# Main.net
KiCad netlist of a schematic drawn in Altium Designer
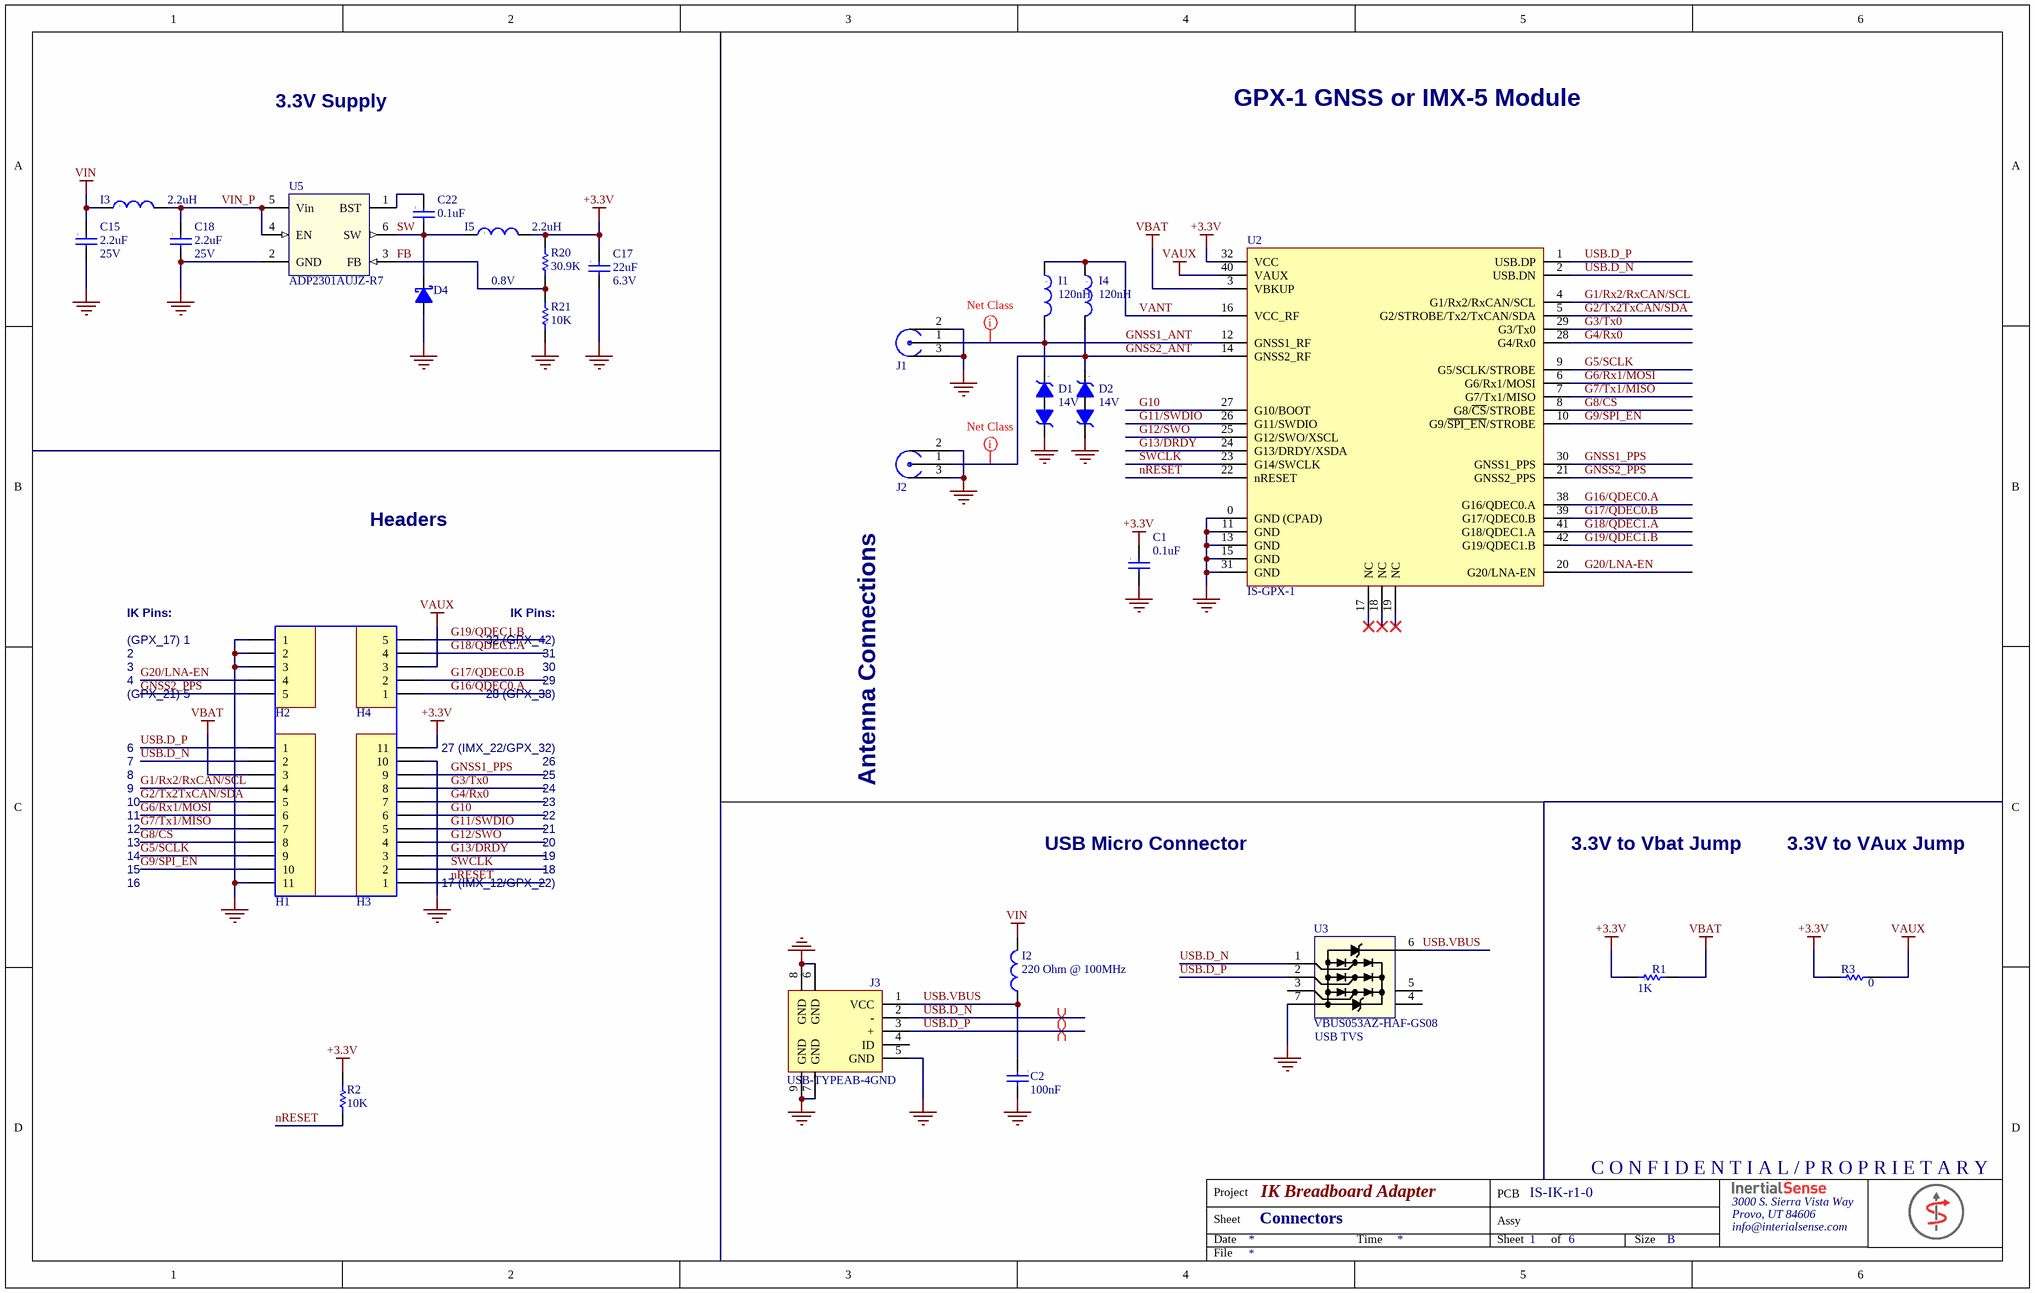
[diagram p0: Main.SchDoc]

(export (version "E")
  (design (tool "Eeschema 10.0.6"))
  (components
    (comp (ref "C1")
      (value "0.1uF")
      (footprint "0402")
      (description "CAP CER .10UF 50V X7R 10% 0402")
      (fields
        (field (name "MANUFACTURER") "TDK Corporation")
        (field (name "MANUFACTURER PART NUMBER") "C1005X7R1H104K")
        (field (name "PUBLISHER") "Altium Limited")
      )
      (libsource (lib "General") (part "Cap"))
    )
    (comp (ref "C2")
      (value "100nF")
      (footprint "0402")
      (description "CAP CER .10UF 50V X7R 10% 0402")
      (fields
        (field (name "MANUFACTURER") "TDK Corporation")
        (field (name "MANUFACTURER PART NUMBER") "C1005X7R1H104K")
        (field (name "PUBLISHER") "Altium Limited")
      )
      (libsource (lib "General") (part "Cap"))
    )
    (comp (ref "C15")
      (value "2.2uF")
      (footprint "0603")
      (description "CAP CER 2.2UF 25V X6S 0603")
      (fields
        (field (name "MANUFACTURER") "Murata")
        (field (name "MANUFACTURER PART NUMBER") "GRT188C81E225KE13D")
        (field (name "VOLTAGE RATING") "25V")
        (field (name "PUBLISHER") "Altium Limited")
      )
      (libsource (lib "General") (part "Cap"))
    )
    (comp (ref "C17")
      (value "22uF")
      (footprint "0603")
      (description "CAP CER 22UF 6.3V X6S 0603")
      (fields
        (field (name "MANUFACTURER") "Murata")
        (field (name "MANUFACTURER PART NUMBER") "GRM188C80J226ME15D")
        (field (name "VOLTAGE RATING") "6.3V")
        (field (name "PUBLISHER") "Altium Limited")
      )
      (libsource (lib "General") (part "Cap"))
    )
    (comp (ref "C18")
      (value "2.2uF")
      (footprint "0603")
      (description "CAP CER 2.2UF 25V X6S 0603")
      (fields
        (field (name "MANUFACTURER") "Murata")
        (field (name "MANUFACTURER PART NUMBER") "GRT188C81E225KE13D")
        (field (name "VOLTAGE RATING") "25V")
        (field (name "PUBLISHER") "Altium Limited")
      )
      (libsource (lib "General") (part "Cap"))
    )
    (comp (ref "C22")
      (value "0.1uF")
      (footprint "0402")
      (description "CAP CER 0.1UF 50V X7R 0402")
      (fields
        (field (name "MANUFACTURER") "TDK")
        (field (name "MANUFACTURER PART NUMBER") "CGA2B3X7R1H104K050BB")
        (field (name "PUBLISHER") "Altium Limited")
      )
      (libsource (lib "General") (part "Cap"))
    )
    (comp (ref "D1")
      (value "Diode - Bidirectional Zener")
      (footprint "R0402")
      (description "LITTELFUSE - PESD0402-140 - DIODE, ESD PROTECTION, 0402, FULL REEL")
      (fields
        (field (name "MANUFACTURER") "Littelfuse")
        (field (name "MANUFACTURER PART NUMBER") "PESD0402-140")
        (field (name "WORKING VOLTAGE") "14V")
      )
      (libsource (lib "General") (part "Diode - Bidirectional Zener"))
    )
    (comp (ref "D2")
      (value "Diode - Bidirectional Zener")
      (footprint "R0402")
      (description "LITTELFUSE - PESD0402-140 - DIODE, ESD PROTECTION, 0402, FULL REEL")
      (fields
        (field (name "MANUFACTURER") "Littelfuse")
        (field (name "MANUFACTURER PART NUMBER") "PESD0402-140")
        (field (name "WORKING VOLTAGE") "14V")
      )
      (libsource (lib "General") (part "Diode - Bidirectional Zener"))
    )
    (comp (ref "D4")
      (value "Diode - Schottky")
      (footprint "D0603B")
      (description "DIODE SCHOTTKY 30V 2A 0603")
      (fields
        (field (name "MANUFACTURER") "Vishay")
        (field (name "MANUFACTURER PART NUMBER") "VSKY20301608-G4-08")
      )
      (libsource (lib "General") (part "Diode - Schottky"))
    )
    (comp (ref "H1")
      (value "Hdr - 11pin")
      (footprint "Header-.1IN-1x11")
      (description "11 pin header")
      (libsource (lib "") (part "Hdr - 11pin_1"))
    )
    (comp (ref "H2")
      (value "Hdr - 5pin")
      (footprint "Header-.1IN-1x5")
      (description "5 pin header")
      (libsource (lib "") (part "Hdr - 5pin_1"))
    )
    (comp (ref "H3")
      (value "Hdr - 11pin")
      (footprint "Header-.1IN-1x11")
      (description "11 pin header")
      (libsource (lib "IS-IG-BB") (part "Hdr - 11pin"))
    )
    (comp (ref "H4")
      (value "Hdr - 5pin")
      (footprint "Header-.1IN-1x5")
      (description "5 pin header")
      (libsource (lib "IS-IG-BB") (part "Hdr - 5pin"))
    )
    (comp (ref "I1")
      (value "120nH")
      (footprint "0402")
      (description "Inductor RF Chip Wirewound 120nH 5% 100MHz 20Q-Factor 110mA 2.66Ohm DCR 0402 Paper T/R")
      (fields
        (field (name "MANUFACTURER") "Murata")
        (field (name "MANUFACTURER PART NUMBER") "LQW15ANR12J00D")
      )
      (libsource (lib "General") (part "Inductor"))
    )
    (comp (ref "I2")
      (value "220 Ohm @ 100MHz")
      (footprint "I0603")
      (description "FERRITE CHIP 220 OHM 2500MA 0603")
      (fields
        (field (name "MANUFACTURER") "Murata Electronics North America")
        (field (name "MANUFACTURER PART NUMBER") "BLM18SG221TN1D")
      )
      (libsource (lib "") (part "Inductor_1"))
    )
    (comp (ref "I3")
      (value "2.2uH")
      (footprint "0806")
      (description "FIXED IND 2.2UH 1.2A 110 MOHM")
      (fields
        (field (name "MANUFACTURER") "TDK")
        (field (name "MANUFACTURER PART NUMBER") "MLP2016H2R2MT0S1")
      )
      (libsource (lib "General") (part "Inductor"))
    )
    (comp (ref "I4")
      (value "120nH")
      (footprint "0402")
      (description "Inductor RF Chip Wirewound 120nH 5% 100MHz 20Q-Factor 110mA 2.66Ohm DCR 0402 Paper T/R")
      (fields
        (field (name "MANUFACTURER") "Murata")
        (field (name "MANUFACTURER PART NUMBER") "LQW15ANR12J00D")
      )
      (libsource (lib "General") (part "Inductor"))
    )
    (comp (ref "I5")
      (value "2.2uH")
      (footprint "0806")
      (description "FIXED IND 2.2UH 1.2A 110 MOHM")
      (fields
        (field (name "MANUFACTURER") "TDK")
        (field (name "MANUFACTURER PART NUMBER") "MLP2016H2R2MT0S1")
      )
      (libsource (lib "General") (part "Inductor"))
    )
    (comp (ref "J1")
      (value "RF - GND x 2")
      (footprint "RF UMC SMD")
      (description "CONN UMC RCPT STR 50 OHM SMD")
      (fields
        (field (name "MANUFACTURER") "Emerson Network Power Connectivity Johnson")
        (field (name "MANUFACTURER PART NUMBER") "128-0711-201")
      )
      (libsource (lib "Connectors") (part "RF - GND x 2"))
    )
    (comp (ref "J2")
      (value "RF - GND x 2")
      (footprint "RF UMC SMD")
      (description "CONN UMC RCPT STR 50 OHM SMD")
      (fields
        (field (name "MANUFACTURER") "Emerson Network Power Connectivity Johnson")
        (field (name "MANUFACTURER PART NUMBER") "128-0711-201")
      )
      (libsource (lib "Connectors") (part "RF - GND x 2"))
    )
    (comp (ref "J3")
      (value "USB-TYPEAB-4GND")
      (footprint "USB Micro AB R/A THR")
      (description "CONN USB AB 4POS")
      (fields
        (field (name "MANUFACTURER") "Amphenol FCI")
        (field (name "MANUFACTURER PART NUMBER") "10118194-0001LF")
      )
      (libsource (lib "Connectors") (part "USB-TYPEAB-4GND"))
    )
    (comp (ref "R1")
      (value "1K")
      (footprint "R0402")
      (description "1 kOhms ±1% 0.063W, 1/16W Chip Resistor 0402 (1005 Metric) Moisture Resistant Thick Film")
      (fields
        (field (name "MANUFACTURER") "Yageo")
        (field (name "MANUFACTURER PART NUMBER") "RC0402FR-071KL")
      )
      (libsource (lib "General") (part "Res"))
    )
    (comp (ref "R2")
      (value "10K")
      (footprint "R0402")
      (description "1 kOhms ±1% 0.063W, 1/16W Chip Resistor 0402 (1005 Metric) Moisture Resistant Thick Film")
      (fields
        (field (name "MANUFACTURER") "Stackpole Electronics")
        (field (name "MANUFACTURER PART NUMBER") "RMCF0402FT10K0")
      )
      (libsource (lib "General") (part "Res"))
    )
    (comp (ref "R3")
      (value "0")
      (footprint "R0402")
      (description "1 kOhms ±1% 0.063W, 1/16W Chip Resistor 0402 (1005 Metric) Moisture Resistant Thick Film")
      (fields
        (field (name "MANUFACTURER") "Yageo")
        (field (name "MANUFACTURER PART NUMBER") "RC0402FR-071KL")
      )
      (libsource (lib "General") (part "Res"))
    )
    (comp (ref "R20")
      (value "30.9K")
      (footprint "R0402")
      (description "RES TF 30.9K OHM 1% 1/16W 0402")
      (fields
        (field (name "MANUFACTURER") "Stackpole Electronics Inc")
        (field (name "MANUFACTURER PART NUMBER") "RMCF0402FT30K9")
      )
      (libsource (lib "General") (part "Res"))
    )
    (comp (ref "R21")
      (value "10K")
      (footprint "R0402")
      (description "RES 10.0K OHM 1/16W 1% 0402 SMD")
      (fields
        (field (name "MANUFACTURER") "Yageo")
        (field (name "MANUFACTURER PART NUMBER") "RC0402FR-0710KL")
      )
      (libsource (lib "General") (part "Res"))
    )
    (comp (ref "U2")
      (value "GPX")
      (footprint "IS-GPX-1.0")
      (description "Inertial Sense GPX")
      (fields
        (field (name "MANUFACTURER") "Inertial Sense")
        (field (name "MANUFACTURER PART NUMBER") "IS-GPX-1")
      )
      (libsource (lib "IS-GPX-1") (part "IS-GPX-1.0"))
    )
    (comp (ref "U3")
      (value "VBUS053")
      (footprint "QFN50P160X160X60-6N")
      (description "ESD SUPPRESS 5.5V 36W 3-Line USB")
      (fields
        (field (name "MANUFACTURER") "Vishay Semiconductors")
        (field (name "MANUFACTURER PART NUMBER") "VBUS053AZ-HAF-GS08")
      )
      (libsource (lib "ICs") (part "VBUS053"))
    )
    (comp (ref "U5")
      (value "ADP2301")
      (footprint "MO-178-AB")
      (description "IC BUCK ADJ 1.2A 6TSOT")
      (fields
        (field (name "MANUFACTURER") "Analog Devices Inc")
        (field (name "MANUFACTURER PART NUMBER") "ADP2301AUJZ-R7")
      )
      (libsource (lib "ICs") (part "ADP2301"))
    )
  )
  (nets
    (net (code "1") (name "+3.3V") (class "Default")
      (node (ref "C1") (pin "1") (pinfunction "1_1") (pintype "passive"))
      (node (ref "C17") (pin "1") (pinfunction "1_1") (pintype "passive"))
      (node (ref "H3") (pin "11") (pinfunction "11_11") (pintype "passive"))
      (node (ref "I5") (pin "2") (pinfunction "2_2") (pintype "passive"))
      (node (ref "R1") (pin "1") (pinfunction "1_1") (pintype "passive"))
      (node (ref "R2") (pin "1") (pinfunction "1_1") (pintype "passive"))
      (node (ref "R20") (pin "2") (pinfunction "2_2") (pintype "passive"))
      (node (ref "R3") (pin "1") (pinfunction "1_1") (pintype "passive"))
      (node (ref "U2") (pin "32") (pinfunction "VCC_32") (pintype "power_in"))
    )
    (net (code "2") (name "/FB") (class "Default")
      (node (ref "R20") (pin "1") (pinfunction "1_1") (pintype "passive"))
      (node (ref "R21") (pin "2") (pinfunction "2_2") (pintype "passive"))
      (node (ref "U5") (pin "3") (pinfunction "FB_3") (pintype "input"))
    )
    (net (code "3") (name "/G1{slash}Rx2{slash}RxCAN{slash}SCL") (class "Default")
      (node (ref "H1") (pin "4") (pinfunction "4_4") (pintype "passive"))
      (node (ref "U2") (pin "4") (pinfunction "G1/Rx2/RxCAN/SCL_4") (pintype "passive"))
    )
    (net (code "4") (name "/G2{slash}Tx2TxCAN{slash}SDA") (class "Default")
      (node (ref "H1") (pin "5") (pinfunction "5_5") (pintype "passive"))
      (node (ref "U2") (pin "5") (pinfunction "G2/STROBE/Tx2/TxCAN/SDA_5") (pintype "passive"))
    )
    (net (code "5") (name "/G3{slash}Tx0") (class "Default")
      (node (ref "H3") (pin "8") (pinfunction "8_8") (pintype "passive"))
      (node (ref "U2") (pin "29") (pinfunction "G3/Tx0_29") (pintype "passive"))
    )
    (net (code "6") (name "/G4{slash}Rx0") (class "Default")
      (node (ref "H3") (pin "7") (pinfunction "7_7") (pintype "passive"))
      (node (ref "U2") (pin "28") (pinfunction "G4/Rx0_28") (pintype "passive"))
    )
    (net (code "7") (name "/G5{slash}SCLK") (class "Default")
      (node (ref "H1") (pin "9") (pinfunction "9_9") (pintype "passive"))
      (node (ref "U2") (pin "9") (pinfunction "G5/SCLK/STROBE_9") (pintype "passive"))
    )
    (net (code "8") (name "/G6{slash}Rx1{slash}MOSI") (class "Default")
      (node (ref "H1") (pin "6") (pinfunction "6_6") (pintype "passive"))
      (node (ref "U2") (pin "6") (pinfunction "G6/Rx1/MOSI_6") (pintype "passive"))
    )
    (net (code "9") (name "/G7{slash}Tx1{slash}MISO") (class "Default")
      (node (ref "H1") (pin "7") (pinfunction "7_7") (pintype "passive"))
      (node (ref "U2") (pin "7") (pinfunction "G7/Tx1/MISO_7") (pintype "passive"))
    )
    (net (code "10") (name "/G8{slash}~{CS}") (class "Default")
      (node (ref "H1") (pin "8") (pinfunction "8_8") (pintype "passive"))
      (node (ref "U2") (pin "8") (pinfunction "G8/~{CS}/STROBE_8") (pintype "passive"))
    )
    (net (code "11") (name "/G9{slash}~{SPI_EN}") (class "Default")
      (node (ref "H1") (pin "10") (pinfunction "10_10") (pintype "passive"))
      (node (ref "U2") (pin "10") (pinfunction "G9/~{SPI_EN}/STROBE_10") (pintype "passive"))
    )
    (net (code "12") (name "/G10") (class "Default")
      (node (ref "H3") (pin "6") (pinfunction "6_6") (pintype "passive"))
      (node (ref "U2") (pin "27") (pinfunction "G10/BOOT_27") (pintype "passive"))
    )
    (net (code "13") (name "/G11{slash}SWDIO") (class "Default")
      (node (ref "H3") (pin "5") (pinfunction "5_5") (pintype "passive"))
      (node (ref "U2") (pin "26") (pinfunction "G11/SWDIO_26") (pintype "passive"))
    )
    (net (code "14") (name "/G12{slash}SWO") (class "Default")
      (node (ref "H3") (pin "4") (pinfunction "4_4") (pintype "passive"))
      (node (ref "U2") (pin "25") (pinfunction "G12/SWO/XSCL_25") (pintype "passive"))
    )
    (net (code "15") (name "/G13{slash}DRDY") (class "Default")
      (node (ref "H3") (pin "3") (pinfunction "3_3") (pintype "passive"))
      (node (ref "U2") (pin "24") (pinfunction "G13/DRDY/XSDA_24") (pintype "passive"))
    )
    (net (code "16") (name "/G16{slash}QDEC0.A") (class "Default")
      (node (ref "H4") (pin "1") (pinfunction "1_1") (pintype "passive"))
      (node (ref "U2") (pin "38") (pinfunction "G16/QDEC0.A_38") (pintype "passive"))
    )
    (net (code "17") (name "/G17{slash}QDEC0.B") (class "Default")
      (node (ref "H4") (pin "2") (pinfunction "2_2") (pintype "passive"))
      (node (ref "U2") (pin "39") (pinfunction "G17/QDEC0.B_39") (pintype "passive"))
    )
    (net (code "18") (name "/G18{slash}QDEC1.A") (class "Default")
      (node (ref "H4") (pin "4") (pinfunction "4_4") (pintype "passive"))
      (node (ref "U2") (pin "41") (pinfunction "G18/QDEC1.A_41") (pintype "passive"))
    )
    (net (code "19") (name "/G19{slash}QDEC1.B") (class "Default")
      (node (ref "H4") (pin "5") (pinfunction "5_5") (pintype "passive"))
      (node (ref "U2") (pin "42") (pinfunction "G19/QDEC1.B_42") (pintype "passive"))
    )
    (net (code "20") (name "/G20{slash}LNA-EN") (class "Default")
      (node (ref "H2") (pin "4") (pinfunction "4_4") (pintype "passive"))
      (node (ref "U2") (pin "20") (pinfunction "G20/LNA-EN_20") (pintype "passive"))
    )
    (net (code "21") (name "/GNSS1_ANT") (class "Default")
      (node (ref "D1") (pin "1") (pinfunction "1_1") (pintype "passive"))
      (node (ref "I1") (pin "2") (pinfunction "2_2") (pintype "passive"))
      (node (ref "J1") (pin "1") (pinfunction "1_1") (pintype "passive"))
      (node (ref "U2") (pin "12") (pinfunction "GNSS1_RF_12") (pintype "passive"))
    )
    (net (code "22") (name "/GNSS1_PPS") (class "Default")
      (node (ref "H3") (pin "9") (pinfunction "9_9") (pintype "passive"))
      (node (ref "U2") (pin "30") (pinfunction "GNSS1_PPS_30") (pintype "passive"))
    )
    (net (code "23") (name "/GNSS2_ANT") (class "Default")
      (node (ref "D2") (pin "1") (pinfunction "1_1") (pintype "passive"))
      (node (ref "I4") (pin "2") (pinfunction "2_2") (pintype "passive"))
      (node (ref "J2") (pin "1") (pinfunction "1_1") (pintype "passive"))
      (node (ref "U2") (pin "14") (pinfunction "GNSS2_RF_14") (pintype "passive"))
    )
    (net (code "24") (name "/GNSS2_PPS") (class "Default")
      (node (ref "H2") (pin "5") (pinfunction "5_5") (pintype "passive"))
      (node (ref "U2") (pin "21") (pinfunction "GNSS2_PPS_21") (pintype "passive"))
    )
    (net (code "25") (name "/SW") (class "Default")
      (node (ref "C22") (pin "2") (pinfunction "2_2") (pintype "passive"))
      (node (ref "D4") (pin "C") (pinfunction "C_C") (pintype "passive"))
      (node (ref "I5") (pin "1") (pinfunction "1_1") (pintype "passive"))
      (node (ref "U5") (pin "6") (pinfunction "SW_6") (pintype "output"))
    )
    (net (code "26") (name "/SWCLK") (class "Default")
      (node (ref "H3") (pin "2") (pinfunction "2_2") (pintype "passive"))
      (node (ref "U2") (pin "23") (pinfunction "G14/SWCLK_23") (pintype "passive"))
    )
    (net (code "27") (name "/USB.D_N") (class "Default")
      (node (ref "H1") (pin "2") (pinfunction "2_2") (pintype "passive"))
      (node (ref "J3") (pin "2") (pinfunction "-_2") (pintype "passive"))
      (node (ref "U2") (pin "2") (pinfunction "USB.DN_2") (pintype "passive"))
      (node (ref "U3") (pin "1") (pintype "passive"))
    )
    (net (code "28") (name "/USB.D_P") (class "Default")
      (node (ref "H1") (pin "1") (pinfunction "1_1") (pintype "passive"))
      (node (ref "J3") (pin "3") (pinfunction "+_3") (pintype "passive"))
      (node (ref "U2") (pin "1") (pinfunction "USB.DP_1") (pintype "passive"))
      (node (ref "U3") (pin "2") (pintype "passive"))
    )
    (net (code "29") (name "/USB.VBUS") (class "Default")
      (node (ref "C2") (pin "1") (pinfunction "1_1") (pintype "passive"))
      (node (ref "I2") (pin "2") (pinfunction "2_2") (pintype "passive"))
      (node (ref "J3") (pin "1") (pinfunction "VCC_1") (pintype "passive"))
      (node (ref "U3") (pin "6") (pintype "passive"))
    )
    (net (code "30") (name "/VANT") (class "Default")
      (node (ref "I1") (pin "1") (pinfunction "1_1") (pintype "passive"))
      (node (ref "I4") (pin "1") (pinfunction "1_1") (pintype "passive"))
      (node (ref "U2") (pin "16") (pinfunction "VCC_RF_16") (pintype "power_in"))
    )
    (net (code "31") (name "/VIN_P") (class "Default")
      (node (ref "C18") (pin "1") (pinfunction "1_1") (pintype "passive"))
      (node (ref "I3") (pin "2") (pinfunction "2_2") (pintype "passive"))
      (node (ref "U5") (pin "4") (pinfunction "EN_4") (pintype "input"))
      (node (ref "U5") (pin "5") (pinfunction "Vin_5") (pintype "power_in"))
    )
    (net (code "32") (name "/nRESET") (class "Default")
      (node (ref "H3") (pin "1") (pinfunction "1_1") (pintype "passive"))
      (node (ref "R2") (pin "2") (pinfunction "2_2") (pintype "passive"))
      (node (ref "U2") (pin "22") (pinfunction "nRESET_22") (pintype "passive"))
    )
    (net (code "33") (name "GND") (class "Default")
      (node (ref "C1") (pin "2") (pinfunction "2_2") (pintype "passive"))
      (node (ref "C15") (pin "2") (pinfunction "2_2") (pintype "passive"))
      (node (ref "C17") (pin "2") (pinfunction "2_2") (pintype "passive"))
      (node (ref "C18") (pin "2") (pinfunction "2_2") (pintype "passive"))
      (node (ref "C2") (pin "2") (pinfunction "2_2") (pintype "passive"))
      (node (ref "D1") (pin "2") (pinfunction "2_2") (pintype "passive"))
      (node (ref "D2") (pin "2") (pinfunction "2_2") (pintype "passive"))
      (node (ref "D4") (pin "A") (pinfunction "A_A") (pintype "passive"))
      (node (ref "H1") (pin "11") (pinfunction "11_11") (pintype "passive"))
      (node (ref "H2") (pin "1") (pinfunction "1_1") (pintype "passive"))
      (node (ref "H2") (pin "2") (pinfunction "2_2") (pintype "passive"))
      (node (ref "H2") (pin "3") (pinfunction "3_3") (pintype "passive"))
      (node (ref "H3") (pin "10") (pinfunction "10_10") (pintype "passive"))
      (node (ref "J1") (pin "2") (pinfunction "2_2") (pintype "passive"))
      (node (ref "J1") (pin "3") (pinfunction "3_3") (pintype "passive"))
      (node (ref "J2") (pin "2") (pinfunction "2_2") (pintype "passive"))
      (node (ref "J2") (pin "3") (pinfunction "3_3") (pintype "passive"))
      (node (ref "J3") (pin "5") (pinfunction "GND_5") (pintype "passive"))
      (node (ref "J3") (pin "6") (pinfunction "GND_6") (pintype "passive"))
      (node (ref "J3") (pin "7") (pinfunction "GND_7") (pintype "passive"))
      (node (ref "J3") (pin "8") (pinfunction "GND_8") (pintype "passive"))
      (node (ref "J3") (pin "9") (pinfunction "GND_9") (pintype "passive"))
      (node (ref "R21") (pin "1") (pinfunction "1_1") (pintype "passive"))
      (node (ref "U2") (pin "0") (pinfunction "GND_(CPAD)_0") (pintype "power_in"))
      (node (ref "U2") (pin "11") (pinfunction "GND_11") (pintype "power_in"))
      (node (ref "U2") (pin "13") (pinfunction "GND_13") (pintype "power_in"))
      (node (ref "U2") (pin "15") (pinfunction "GND_15") (pintype "power_in"))
      (node (ref "U2") (pin "31") (pinfunction "GND_31") (pintype "power_in"))
      (node (ref "U3") (pin "7") (pintype "passive"))
      (node (ref "U5") (pin "2") (pinfunction "GND_2") (pintype "power_in"))
    )
    (net (code "34") (name "Net-(U5-BST)") (class "Default")
      (node (ref "C22") (pin "1") (pinfunction "1_1") (pintype "passive"))
      (node (ref "U5") (pin "1") (pinfunction "BST_1") (pintype "passive"))
    )
    (net (code "35") (name "VAUX") (class "Default")
      (node (ref "H4") (pin "3") (pinfunction "3_3") (pintype "passive"))
      (node (ref "R3") (pin "2") (pinfunction "2_2") (pintype "passive"))
      (node (ref "U2") (pin "40") (pinfunction "VAUX_40") (pintype "power_in"))
    )
    (net (code "36") (name "VBAT") (class "Default")
      (node (ref "H1") (pin "3") (pinfunction "3_3") (pintype "passive"))
      (node (ref "R1") (pin "2") (pinfunction "2_2") (pintype "passive"))
      (node (ref "U2") (pin "3") (pinfunction "VBKUP_3") (pintype "passive"))
    )
    (net (code "37") (name "VIN") (class "Default")
      (node (ref "C15") (pin "1") (pinfunction "1_1") (pintype "passive"))
      (node (ref "I2") (pin "1") (pinfunction "1_1") (pintype "passive"))
      (node (ref "I3") (pin "1") (pinfunction "1_1") (pintype "passive"))
    )
    (net (code "38") (name "unconnected-(J3-ID-Pad4)") (class "Default")
      (node (ref "J3") (pin "4") (pinfunction "ID_4") (pintype "passive"))
    )
    (net (code "39") (name "unconnected-(U2-NC-Pad17)") (class "Default")
      (node (ref "U2") (pin "17") (pinfunction "NC_17") (pintype "passive+no_connect"))
    )
    (net (code "40") (name "unconnected-(U2-NC-Pad18)") (class "Default")
      (node (ref "U2") (pin "18") (pinfunction "NC_18") (pintype "passive+no_connect"))
    )
    (net (code "41") (name "unconnected-(U2-NC-Pad19)") (class "Default")
      (node (ref "U2") (pin "19") (pinfunction "NC_19") (pintype "passive+no_connect"))
    )
    (net (code "42") (name "unconnected-(U3-Pad3)") (class "Default")
      (node (ref "U3") (pin "3") (pintype "passive"))
    )
    (net (code "43") (name "unconnected-(U3-nc-Pad4)") (class "Default")
      (node (ref "U3") (pin "4") (pinfunction "nc_4") (pintype "passive"))
    )
    (net (code "44") (name "unconnected-(U3-nc-Pad5)") (class "Default")
      (node (ref "U3") (pin "5") (pinfunction "nc_5") (pintype "passive"))
    )
  )
)
